# eagle.net
KiCad netlist of a schematic drawn in EAGLE
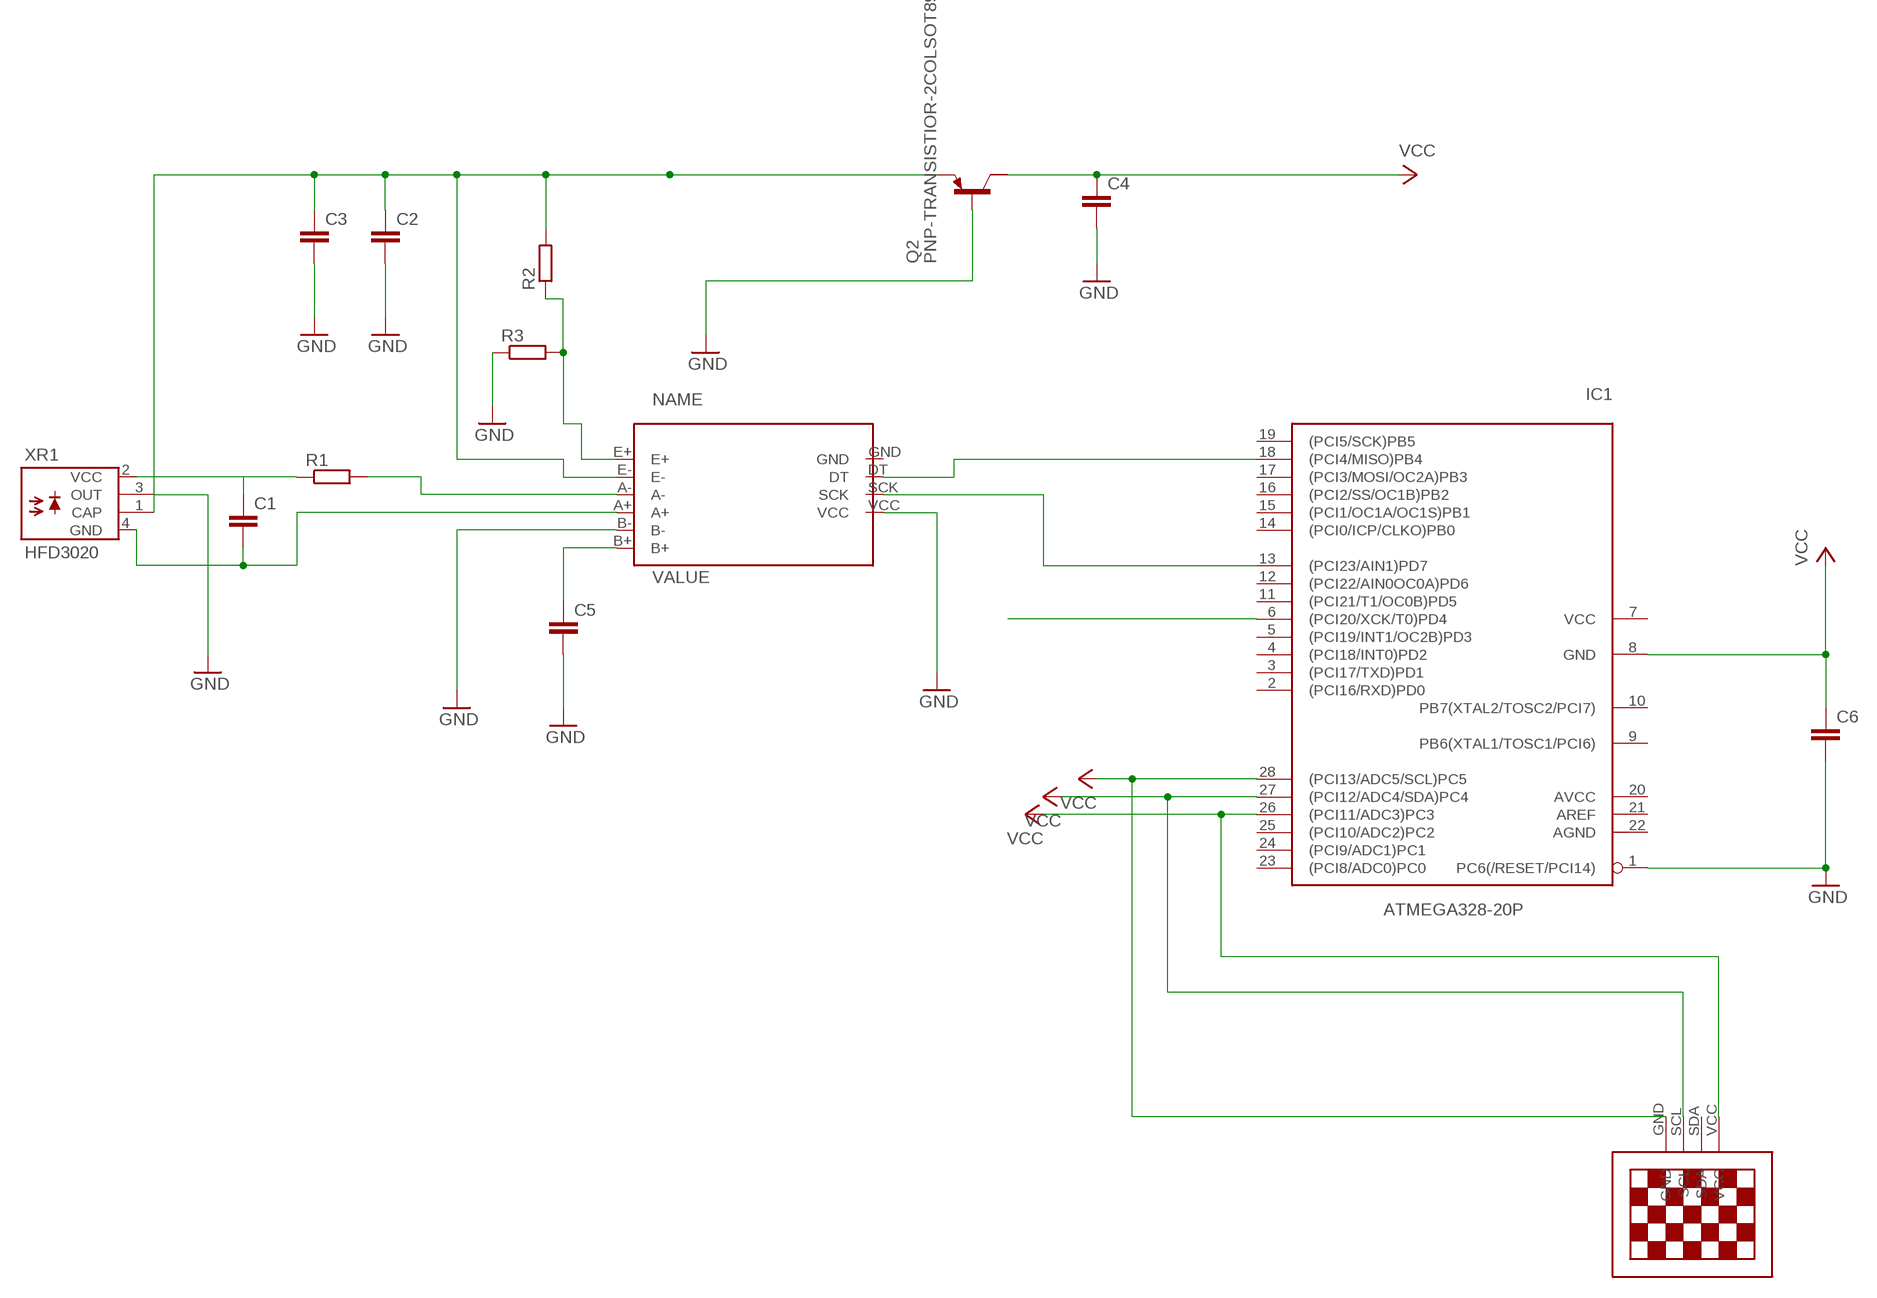
[diagram p0: schematic, sheet 1]

(export (version "E")
  (design (tool "Eeschema 10.0.6"))
  (components
    (comp (ref "C1")
      (value "C2,5-3")
      (footprint "eagle-import:C2.5-3")
      (libsource (lib "eagle-import") (part "C2,5-3"))
    )
    (comp (ref "C2")
      (value "C2,5-3")
      (footprint "eagle-import:C2.5-3")
      (libsource (lib "eagle-import") (part "C2,5-3"))
    )
    (comp (ref "C3")
      (value "C2,5-3")
      (footprint "eagle-import:C2.5-3")
      (libsource (lib "eagle-import") (part "C2,5-3"))
    )
    (comp (ref "C4")
      (value "C2,5-3")
      (footprint "eagle-import:C2.5-3")
      (libsource (lib "eagle-import") (part "C2,5-3"))
    )
    (comp (ref "C5")
      (value "C2,5-3")
      (footprint "eagle-import:C2.5-3")
      (libsource (lib "eagle-import") (part "C2,5-3"))
    )
    (comp (ref "C6")
      (value "C2,5-3")
      (footprint "eagle-import:C2.5-3")
      (libsource (lib "eagle-import") (part "C2,5-3"))
    )
    (comp (ref "IC1")
      (value "ATMEGA328-20P")
      (footprint "eagle-import:DIL28-3")
      (libsource (lib "eagle-import") (part "ATMEGA328P-20"))
    )
    (comp (ref "Q2")
      (value "PNP-TRANSISTIOR-2COLSOT89")
      (footprint "eagle-import:SOT89")
      (libsource (lib "eagle-import") (part "PNP-TRANSISTIOR-2COLSOT89"))
    )
    (comp (ref "R1")
      (value "R-EU_0204/2V")
      (footprint "eagle-import:0204V")
      (libsource (lib "eagle-import") (part "R-EU_0204/2V"))
    )
    (comp (ref "R2")
      (value "R-EU_0204/2V")
      (footprint "eagle-import:0204V")
      (libsource (lib "eagle-import") (part "R-EU_0204/2V"))
    )
    (comp (ref "R3")
      (value "R-EU_0204/2V")
      (footprint "eagle-import:0204V")
      (libsource (lib "eagle-import") (part "R-EU_0204/2V"))
    )
    (comp (ref "U$1")
      (value "13\"OLED13\"OLED")
      (footprint "eagle-import:1.3_OLED")
      (libsource (lib "eagle-import") (part "13{dblquote}OLED13{dblquote}OLED"))
    )
    (comp (ref "U$2")
      (value "HX711A")
      (footprint "eagle-import:HX711")
      (libsource (lib "eagle-import") (part "HX711A"))
    )
    (comp (ref "XR1")
      (value "HFD3020")
      (footprint "eagle-import:TO18PL4")
      (fields (field (name "MPN") "HFD3020-500-BBA"))
      (libsource (lib "eagle-import") (part "HFD3020"))
    )
  )
  (nets
    (net (code "1") (name "GND") (class "Default")
      (node (ref "C2") (pin "2") (pinfunction "2_2") (pintype "passive"))
      (node (ref "C3") (pin "2") (pinfunction "2_2") (pintype "passive"))
      (node (ref "C4") (pin "2") (pinfunction "2_2") (pintype "passive"))
      (node (ref "C5") (pin "2") (pinfunction "2_2") (pintype "passive"))
      (node (ref "C6") (pin "2") (pinfunction "2_2") (pintype "passive"))
      (node (ref "IC1") (pin "1") (pinfunction "PC6(/RESET/PCI14)_1") (pintype "bidirectional"))
      (node (ref "Q2") (pin "1") (pinfunction "B_1") (pintype "passive"))
      (node (ref "R3") (pin "1") (pinfunction "1_1") (pintype "passive"))
      (node (ref "U$2") (pin "B-") (pinfunction "B-_B-") (pintype "bidirectional"))
      (node (ref "U$2") (pin "VCC") (pinfunction "VCC_VCC") (pintype "bidirectional"))
      (node (ref "XR1") (pin "3") (pinfunction "OUT_3") (pintype "output"))
    )
    (net (code "2") (name "Net-(C5-Pad1)") (class "Default")
      (node (ref "C5") (pin "1") (pinfunction "1_1") (pintype "passive"))
      (node (ref "U$2") (pin "B+") (pinfunction "B+_B+") (pintype "bidirectional"))
    )
    (net (code "3") (name "Net-(IC1-(PCI4{slash}MISO)PB4)") (class "Default")
      (node (ref "IC1") (pin "18") (pinfunction "(PCI4/MISO)PB4_18") (pintype "bidirectional"))
      (node (ref "U$2") (pin "DT") (pinfunction "DT_DT") (pintype "bidirectional"))
    )
    (net (code "4") (name "Net-(IC1-(PCI23{slash}AIN1)PD7)") (class "Default")
      (node (ref "IC1") (pin "13") (pinfunction "(PCI23/AIN1)PD7_13") (pintype "bidirectional"))
      (node (ref "U$2") (pin "SCK") (pinfunction "SCK_SCK") (pintype "bidirectional"))
    )
    (net (code "5") (name "Net-(Q2-E)") (class "Default")
      (node (ref "C2") (pin "1") (pinfunction "1_1") (pintype "passive"))
      (node (ref "C3") (pin "1") (pinfunction "1_1") (pintype "passive"))
      (node (ref "Q2") (pin "3") (pinfunction "E_3") (pintype "passive"))
      (node (ref "R2") (pin "2") (pinfunction "2_2") (pintype "passive"))
      (node (ref "U$2") (pin "E-") (pinfunction "E-_E-") (pintype "bidirectional"))
      (node (ref "XR1") (pin "1") (pinfunction "CAP_1") (pintype "output"))
    )
    (net (code "6") (name "Net-(R1-Pad2)") (class "Default")
      (node (ref "R1") (pin "2") (pinfunction "2_2") (pintype "passive"))
      (node (ref "U$2") (pin "A-") (pinfunction "A-_A-") (pintype "bidirectional"))
    )
    (net (code "7") (name "Net-(R2-Pad1)") (class "Default")
      (node (ref "R2") (pin "1") (pinfunction "1_1") (pintype "passive"))
      (node (ref "R3") (pin "2") (pinfunction "2_2") (pintype "passive"))
      (node (ref "U$2") (pin "E+") (pinfunction "E+_E+") (pintype "bidirectional"))
    )
    (net (code "8") (name "Net-(XR1-GND)") (class "Default")
      (node (ref "C1") (pin "2") (pinfunction "2_2") (pintype "passive"))
      (node (ref "U$2") (pin "A+") (pinfunction "A+_A+") (pintype "bidirectional"))
      (node (ref "XR1") (pin "4") (pinfunction "GND_4") (pintype "power_in"))
    )
    (net (code "9") (name "Net-(XR1-VCC)") (class "Default")
      (node (ref "R1") (pin "1") (pinfunction "1_1") (pintype "passive"))
      (node (ref "XR1") (pin "2") (pinfunction "VCC_2") (pintype "power_in"))
    )
    (net (code "10") (name "VCC") (class "Default")
      (node (ref "C4") (pin "1") (pinfunction "1_1") (pintype "passive"))
      (node (ref "C6") (pin "1") (pinfunction "1_1") (pintype "passive"))
      (node (ref "IC1") (pin "26") (pinfunction "(PCI11/ADC3)PC3_26") (pintype "bidirectional"))
      (node (ref "IC1") (pin "27") (pinfunction "(PCI12/ADC4/SDA)PC4_27") (pintype "bidirectional"))
      (node (ref "IC1") (pin "28") (pinfunction "(PCI13/ADC5/SCL)PC5_28") (pintype "bidirectional"))
      (node (ref "IC1") (pin "8") (pinfunction "GND_8") (pintype "bidirectional"))
      (node (ref "Q2") (pin "2") (pinfunction "C_2") (pintype "passive"))
      (node (ref "U$1") (pin "GND") (pinfunction "GND_GND") (pintype "bidirectional"))
      (node (ref "U$1") (pin "SCL") (pinfunction "SCL_SCL") (pintype "bidirectional"))
      (node (ref "U$1") (pin "VCC") (pinfunction "VCC_VCC") (pintype "bidirectional"))
    )
    (net (code "11") (name "unconnected-(C1-Pad1)") (class "Default")
      (node (ref "C1") (pin "1") (pinfunction "1_1") (pintype "passive"))
    )
    (net (code "12") (name "unconnected-(IC1-(PCI0{slash}ICP{slash}CLKO)PB0-Pad14)") (class "Default")
      (node (ref "IC1") (pin "14") (pinfunction "(PCI0/ICP/CLKO)PB0_14") (pintype "bidirectional"))
    )
    (net (code "13") (name "unconnected-(IC1-(PCI1{slash}OC1A{slash}OC1S)PB1-Pad15)") (class "Default")
      (node (ref "IC1") (pin "15") (pinfunction "(PCI1/OC1A/OC1S)PB1_15") (pintype "bidirectional"))
    )
    (net (code "14") (name "unconnected-(IC1-(PCI2{slash}SS{slash}OC1B)PB2-Pad16)") (class "Default")
      (node (ref "IC1") (pin "16") (pinfunction "(PCI2/SS/OC1B)PB2_16") (pintype "bidirectional"))
    )
    (net (code "15") (name "unconnected-(IC1-(PCI3{slash}MOSI{slash}OC2A)PB3-Pad17)") (class "Default")
      (node (ref "IC1") (pin "17") (pinfunction "(PCI3/MOSI/OC2A)PB3_17") (pintype "bidirectional"))
    )
    (net (code "16") (name "unconnected-(IC1-(PCI5{slash}SCK)PB5-Pad19)") (class "Default")
      (node (ref "IC1") (pin "19") (pinfunction "(PCI5/SCK)PB5_19") (pintype "bidirectional"))
    )
    (net (code "17") (name "unconnected-(IC1-(PCI8{slash}ADC0)PC0-Pad23)") (class "Default")
      (node (ref "IC1") (pin "23") (pinfunction "(PCI8/ADC0)PC0_23") (pintype "bidirectional"))
    )
    (net (code "18") (name "unconnected-(IC1-(PCI9{slash}ADC1)PC1-Pad24)") (class "Default")
      (node (ref "IC1") (pin "24") (pinfunction "(PCI9/ADC1)PC1_24") (pintype "bidirectional"))
    )
    (net (code "19") (name "unconnected-(IC1-(PCI10{slash}ADC2)PC2-Pad25)") (class "Default")
      (node (ref "IC1") (pin "25") (pinfunction "(PCI10/ADC2)PC2_25") (pintype "bidirectional"))
    )
    (net (code "20") (name "unconnected-(IC1-(PCI16{slash}RXD)PD0-Pad2)") (class "Default")
      (node (ref "IC1") (pin "2") (pinfunction "(PCI16/RXD)PD0_2") (pintype "bidirectional"))
    )
    (net (code "21") (name "unconnected-(IC1-(PCI17{slash}TXD)PD1-Pad3)") (class "Default")
      (node (ref "IC1") (pin "3") (pinfunction "(PCI17/TXD)PD1_3") (pintype "bidirectional"))
    )
    (net (code "22") (name "unconnected-(IC1-(PCI18{slash}INT0)PD2-Pad4)") (class "Default")
      (node (ref "IC1") (pin "4") (pinfunction "(PCI18/INT0)PD2_4") (pintype "bidirectional"))
    )
    (net (code "23") (name "unconnected-(IC1-(PCI19{slash}INT1{slash}OC2B)PD3-Pad5)") (class "Default")
      (node (ref "IC1") (pin "5") (pinfunction "(PCI19/INT1/OC2B)PD3_5") (pintype "bidirectional"))
    )
    (net (code "24") (name "unconnected-(IC1-(PCI20{slash}XCK{slash}T0)PD4-Pad6)") (class "Default")
      (node (ref "IC1") (pin "6") (pinfunction "(PCI20/XCK/T0)PD4_6") (pintype "bidirectional"))
    )
    (net (code "25") (name "unconnected-(IC1-(PCI21{slash}T1{slash}OC0B)PD5-Pad11)") (class "Default")
      (node (ref "IC1") (pin "11") (pinfunction "(PCI21/T1/OC0B)PD5_11") (pintype "bidirectional"))
    )
    (net (code "26") (name "unconnected-(IC1-(PCI22{slash}AIN0OC0A)PD6-Pad12)") (class "Default")
      (node (ref "IC1") (pin "12") (pinfunction "(PCI22/AIN0OC0A)PD6_12") (pintype "bidirectional"))
    )
    (net (code "27") (name "unconnected-(IC1-AGND-Pad22)") (class "Default")
      (node (ref "IC1") (pin "22") (pinfunction "AGND_22") (pintype "bidirectional"))
    )
    (net (code "28") (name "unconnected-(IC1-AREF-Pad21)") (class "Default")
      (node (ref "IC1") (pin "21") (pinfunction "AREF_21") (pintype "bidirectional"))
    )
    (net (code "29") (name "unconnected-(IC1-AVCC-Pad20)") (class "Default")
      (node (ref "IC1") (pin "20") (pinfunction "AVCC_20") (pintype "bidirectional"))
    )
    (net (code "30") (name "unconnected-(IC1-PB6(XTAL1{slash}TOSC1{slash}PCI6)-Pad9)") (class "Default")
      (node (ref "IC1") (pin "9") (pinfunction "PB6(XTAL1/TOSC1/PCI6)_9") (pintype "bidirectional"))
    )
    (net (code "31") (name "unconnected-(IC1-PB7(XTAL2{slash}TOSC2{slash}PCI7)-Pad10)") (class "Default")
      (node (ref "IC1") (pin "10") (pinfunction "PB7(XTAL2/TOSC2/PCI7)_10") (pintype "bidirectional"))
    )
    (net (code "32") (name "unconnected-(IC1-VCC-Pad7)") (class "Default")
      (node (ref "IC1") (pin "7") (pinfunction "VCC_7") (pintype "bidirectional"))
    )
    (net (code "33") (name "unconnected-(Q2-C{slash}-Pad2@1)") (class "Default")
      (node (ref "Q2") (pin "2@1") (pinfunction "C/_2@1") (pintype "passive"))
    )
    (net (code "34") (name "unconnected-(U$1-PadSDA)") (class "Default")
      (node (ref "U$1") (pin "SDA") (pinfunction "SDA_SDA") (pintype "bidirectional"))
    )
    (net (code "35") (name "unconnected-(U$2-PadGND)") (class "Default")
      (node (ref "U$2") (pin "GND") (pinfunction "GND_GND") (pintype "bidirectional"))
    )
  )
)
